# Motor.net
KiCad netlist of a schematic drawn in Altium Designer
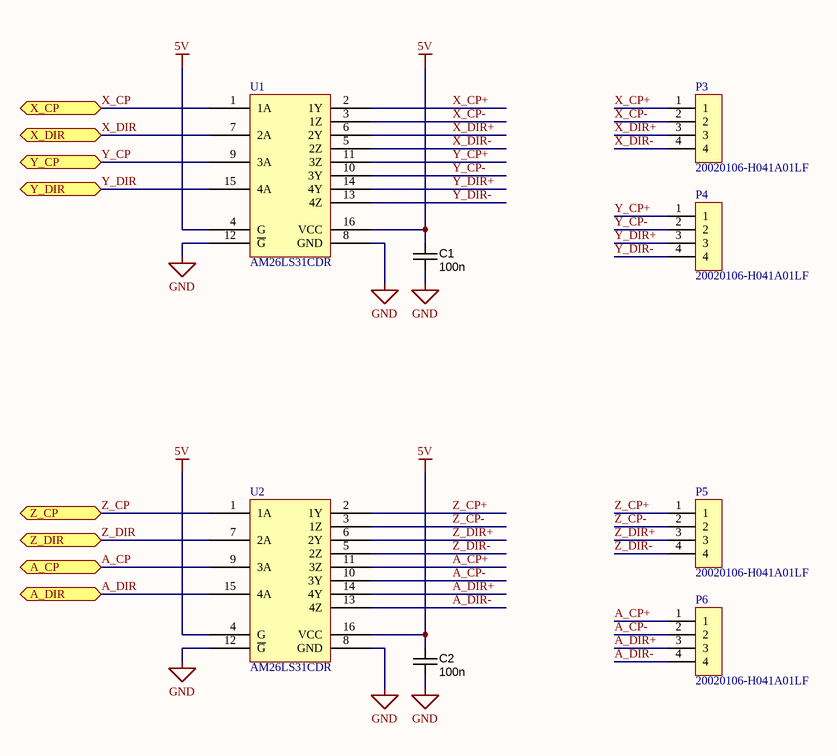
[diagram p0: Motor.SchDoc]

(export (version "E")
  (design (tool "Eeschema 10.0.6"))
  (components
    (comp (ref "C1")
      (value "100n")
      (footprint "IPC-7352 Chip_Capacitor_N:CAPC1608N")
      (description "Capacitor SMD Cer X7R")
      (fields (field (name "TOLERANCE") "?0%"))
      (libsource (lib "LCR Devices") (part "Capacitor SMD Cer X7R"))
    )
    (comp (ref "C2")
      (value "100n")
      (footprint "IPC-7352 Chip_Capacitor_N:CAPC1608N")
      (description "Capacitor SMD Cer X7R")
      (fields (field (name "TOLERANCE") "?0%"))
      (libsource (lib "LCR Devices") (part "Capacitor SMD Cer X7R"))
    )
    (comp (ref "P3")
      (value "20020106-H041A01LF")
      (footprint "Connectors:20020106-H041A01LF")
      (description "TERM BLOCK HDR 4POS VERT 5.08MM")
      (libsource (lib "Connectors") (part "Amphenol FCI"))
    )
    (comp (ref "P4")
      (value "20020106-H041A01LF")
      (footprint "Connectors:20020106-H041A01LF")
      (description "TERM BLOCK HDR 4POS VERT 5.08MM")
      (libsource (lib "Connectors") (part "Amphenol FCI"))
    )
    (comp (ref "P5")
      (value "20020106-H041A01LF")
      (footprint "Connectors:20020106-H041A01LF")
      (description "TERM BLOCK HDR 4POS VERT 5.08MM")
      (libsource (lib "Connectors") (part "Amphenol FCI"))
    )
    (comp (ref "P6")
      (value "20020106-H041A01LF")
      (footprint "Connectors:20020106-H041A01LF")
      (description "TERM BLOCK HDR 4POS VERT 5.08MM")
      (libsource (lib "Connectors") (part "Amphenol FCI"))
    )
    (comp (ref "U1")
      (value "AM26LS31CDR")
      (footprint "Miscellaneous Devices:SOIC16_N")
      (description "IC QUAD DIFF LINE DRIVER 16-SOIC")
      (libsource (lib "Chip") (part "AM26LS31C"))
    )
    (comp (ref "U2")
      (value "AM26LS31CDR")
      (footprint "Miscellaneous Devices:SOIC16_N")
      (description "IC QUAD DIFF LINE DRIVER 16-SOIC")
      (libsource (lib "Chip") (part "AM26LS31C"))
    )
  )
  (nets
    (net (code "1") (name "/A_CP") (class "Default")
      (node (ref "U2") (pin "9") (pinfunction "3A_9") (pintype "passive"))
    )
    (net (code "2") (name "/A_CP+") (class "Default")
      (node (ref "P6") (pin "1") (pinfunction "1_1") (pintype "passive"))
      (node (ref "U2") (pin "11") (pinfunction "3Z_11") (pintype "passive"))
    )
    (net (code "3") (name "/A_CP-") (class "Default")
      (node (ref "P6") (pin "2") (pinfunction "2_2") (pintype "passive"))
      (node (ref "U2") (pin "10") (pinfunction "3Y_10") (pintype "passive"))
    )
    (net (code "4") (name "/A_DIR") (class "Default")
      (node (ref "U2") (pin "15") (pinfunction "4A_15") (pintype "passive"))
    )
    (net (code "5") (name "/A_DIR+") (class "Default")
      (node (ref "P6") (pin "3") (pinfunction "3_3") (pintype "passive"))
      (node (ref "U2") (pin "14") (pinfunction "4Y_14") (pintype "passive"))
    )
    (net (code "6") (name "/A_DIR-") (class "Default")
      (node (ref "P6") (pin "4") (pinfunction "4_4") (pintype "passive"))
      (node (ref "U2") (pin "13") (pinfunction "4Z_13") (pintype "passive"))
    )
    (net (code "7") (name "/X_CP") (class "Default")
      (node (ref "U1") (pin "1") (pinfunction "1A_1") (pintype "passive"))
    )
    (net (code "8") (name "/X_CP+") (class "Default")
      (node (ref "P3") (pin "1") (pinfunction "1_1") (pintype "passive"))
      (node (ref "U1") (pin "2") (pinfunction "1Y_2") (pintype "passive"))
    )
    (net (code "9") (name "/X_CP-") (class "Default")
      (node (ref "P3") (pin "2") (pinfunction "2_2") (pintype "passive"))
      (node (ref "U1") (pin "3") (pinfunction "1Z_3") (pintype "passive"))
    )
    (net (code "10") (name "/X_DIR") (class "Default")
      (node (ref "U1") (pin "7") (pinfunction "2A_7") (pintype "passive"))
    )
    (net (code "11") (name "/X_DIR+") (class "Default")
      (node (ref "P3") (pin "3") (pinfunction "3_3") (pintype "passive"))
      (node (ref "U1") (pin "6") (pinfunction "2Y_6") (pintype "passive"))
    )
    (net (code "12") (name "/X_DIR-") (class "Default")
      (node (ref "P3") (pin "4") (pinfunction "4_4") (pintype "passive"))
      (node (ref "U1") (pin "5") (pinfunction "2Z_5") (pintype "passive"))
    )
    (net (code "13") (name "/Y_CP") (class "Default")
      (node (ref "U1") (pin "9") (pinfunction "3A_9") (pintype "passive"))
    )
    (net (code "14") (name "/Y_CP+") (class "Default")
      (node (ref "P4") (pin "1") (pinfunction "1_1") (pintype "passive"))
      (node (ref "U1") (pin "11") (pinfunction "3Z_11") (pintype "passive"))
    )
    (net (code "15") (name "/Y_CP-") (class "Default")
      (node (ref "P4") (pin "2") (pinfunction "2_2") (pintype "passive"))
      (node (ref "U1") (pin "10") (pinfunction "3Y_10") (pintype "passive"))
    )
    (net (code "16") (name "/Y_DIR") (class "Default")
      (node (ref "U1") (pin "15") (pinfunction "4A_15") (pintype "passive"))
    )
    (net (code "17") (name "/Y_DIR+") (class "Default")
      (node (ref "P4") (pin "3") (pinfunction "3_3") (pintype "passive"))
      (node (ref "U1") (pin "14") (pinfunction "4Y_14") (pintype "passive"))
    )
    (net (code "18") (name "/Y_DIR-") (class "Default")
      (node (ref "P4") (pin "4") (pinfunction "4_4") (pintype "passive"))
      (node (ref "U1") (pin "13") (pinfunction "4Z_13") (pintype "passive"))
    )
    (net (code "19") (name "/Z_CP") (class "Default")
      (node (ref "U2") (pin "1") (pinfunction "1A_1") (pintype "passive"))
    )
    (net (code "20") (name "/Z_CP+") (class "Default")
      (node (ref "P5") (pin "1") (pinfunction "1_1") (pintype "passive"))
      (node (ref "U2") (pin "2") (pinfunction "1Y_2") (pintype "passive"))
    )
    (net (code "21") (name "/Z_CP-") (class "Default")
      (node (ref "P5") (pin "2") (pinfunction "2_2") (pintype "passive"))
      (node (ref "U2") (pin "3") (pinfunction "1Z_3") (pintype "passive"))
    )
    (net (code "22") (name "/Z_DIR") (class "Default")
      (node (ref "U2") (pin "7") (pinfunction "2A_7") (pintype "passive"))
    )
    (net (code "23") (name "/Z_DIR+") (class "Default")
      (node (ref "P5") (pin "3") (pinfunction "3_3") (pintype "passive"))
      (node (ref "U2") (pin "6") (pinfunction "2Y_6") (pintype "passive"))
    )
    (net (code "24") (name "/Z_DIR-") (class "Default")
      (node (ref "P5") (pin "4") (pinfunction "4_4") (pintype "passive"))
      (node (ref "U2") (pin "5") (pinfunction "2Z_5") (pintype "passive"))
    )
    (net (code "25") (name "5V") (class "Default")
      (node (ref "C1") (pin "1") (pintype "passive"))
      (node (ref "C2") (pin "1") (pintype "passive"))
      (node (ref "U1") (pin "16") (pinfunction "VCC_16") (pintype "passive"))
      (node (ref "U1") (pin "4") (pinfunction "G_4") (pintype "passive"))
      (node (ref "U2") (pin "16") (pinfunction "VCC_16") (pintype "passive"))
      (node (ref "U2") (pin "4") (pinfunction "G_4") (pintype "passive"))
    )
    (net (code "26") (name "GND") (class "Default")
      (node (ref "C1") (pin "2") (pintype "passive"))
      (node (ref "C2") (pin "2") (pintype "passive"))
      (node (ref "U1") (pin "12") (pinfunction "~{G}_12") (pintype "passive"))
      (node (ref "U1") (pin "8") (pinfunction "GND_8") (pintype "passive"))
      (node (ref "U2") (pin "12") (pinfunction "~{G}_12") (pintype "passive"))
      (node (ref "U2") (pin "8") (pinfunction "GND_8") (pintype "passive"))
    )
  )
)
